# LightSensor_PCB.net
KiCad netlist of a schematic drawn in Altium Designer
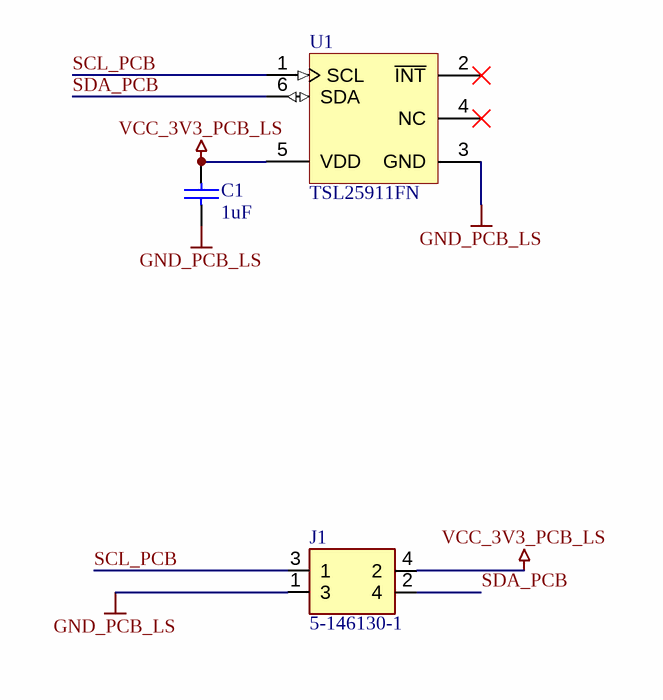
[diagram p0: LightSensor_PCB.SchDoc]

(export (version "E")
  (design (tool "Eeschema 10.0.6"))
  (components
    (comp (ref "C1")
      (value "1uF")
      (footprint "CAPC2013X135X45LL10T25")
      (fields (field (name "MANUFACTURER") "Murata") (field (name "PART NUMBER") "GRM21BR71H105KA12L"))
      (libsource (lib "Altium Content Vault") (part "CAP"))
    )
    (comp (ref "J1")
      (value "5-146130-1")
      (footprint "5-146130-1:TE_5-146130-1")
      (description "AMPMODU 4 Position Surface Mount Dual Row Straight 2.54 mm Breakaway Header")
      (fields (field (name "MF") "{'manufacturer': u'TE Connectivity'}"))
      (libsource (lib "*") (part "5-146130-1"))
    )
    (comp (ref "U1")
      (value "TSL25911FN")
      (footprint "AMS-FN-6-2400X2000DE_V")
      (description "Light-to-Digital Converter with I2C Interface, 2.7 to 3.6 V, -30 to 70 degC, FN-6, Pb-Free, Reel")
      (fields (field (name "MANUFACTURER") "AMS"))
      (libsource (lib "Altium Content Vault") (part "AMS-TSL25911-FN-6"))
    )
  )
  (nets
    (net (code "1") (name "/SCL_PCB") (class "Default")
      (node (ref "J1") (pin "3") (pinfunction "1_3") (pintype "passive"))
      (node (ref "U1") (pin "1") (pinfunction "SCL_1") (pintype "input"))
    )
    (net (code "2") (name "/SDA_PCB") (class "Default")
      (node (ref "J1") (pin "2") (pinfunction "4_2") (pintype "passive"))
      (node (ref "U1") (pin "6") (pinfunction "SDA_6") (pintype "bidirectional"))
    )
    (net (code "3") (name "GND_PCB_LS") (class "Default")
      (node (ref "C1") (pin "2") (pinfunction "2_2") (pintype "passive"))
      (node (ref "J1") (pin "1") (pinfunction "3_1") (pintype "passive"))
      (node (ref "U1") (pin "3") (pinfunction "GND_3") (pintype "power_in"))
    )
    (net (code "4") (name "VCC_3V3_PCB_LS") (class "Default")
      (node (ref "C1") (pin "1") (pinfunction "1_1") (pintype "passive"))
      (node (ref "J1") (pin "4") (pinfunction "2_4") (pintype "passive"))
      (node (ref "U1") (pin "5") (pinfunction "VDD_5") (pintype "power_in"))
    )
    (net (code "5") (name "unconnected-(U1-NC-Pad4)") (class "Default")
      (node (ref "U1") (pin "4") (pinfunction "NC_4") (pintype "passive+no_connect"))
    )
    (net (code "6") (name "unconnected-(U1-~{INT}-Pad2)") (class "Default")
      (node (ref "U1") (pin "2") (pinfunction "~{INT}_2") (pintype "open_collector+no_connect"))
    )
  )
)
